# Amplifier_Output.net
KiCad netlist of a schematic drawn in Altium Designer
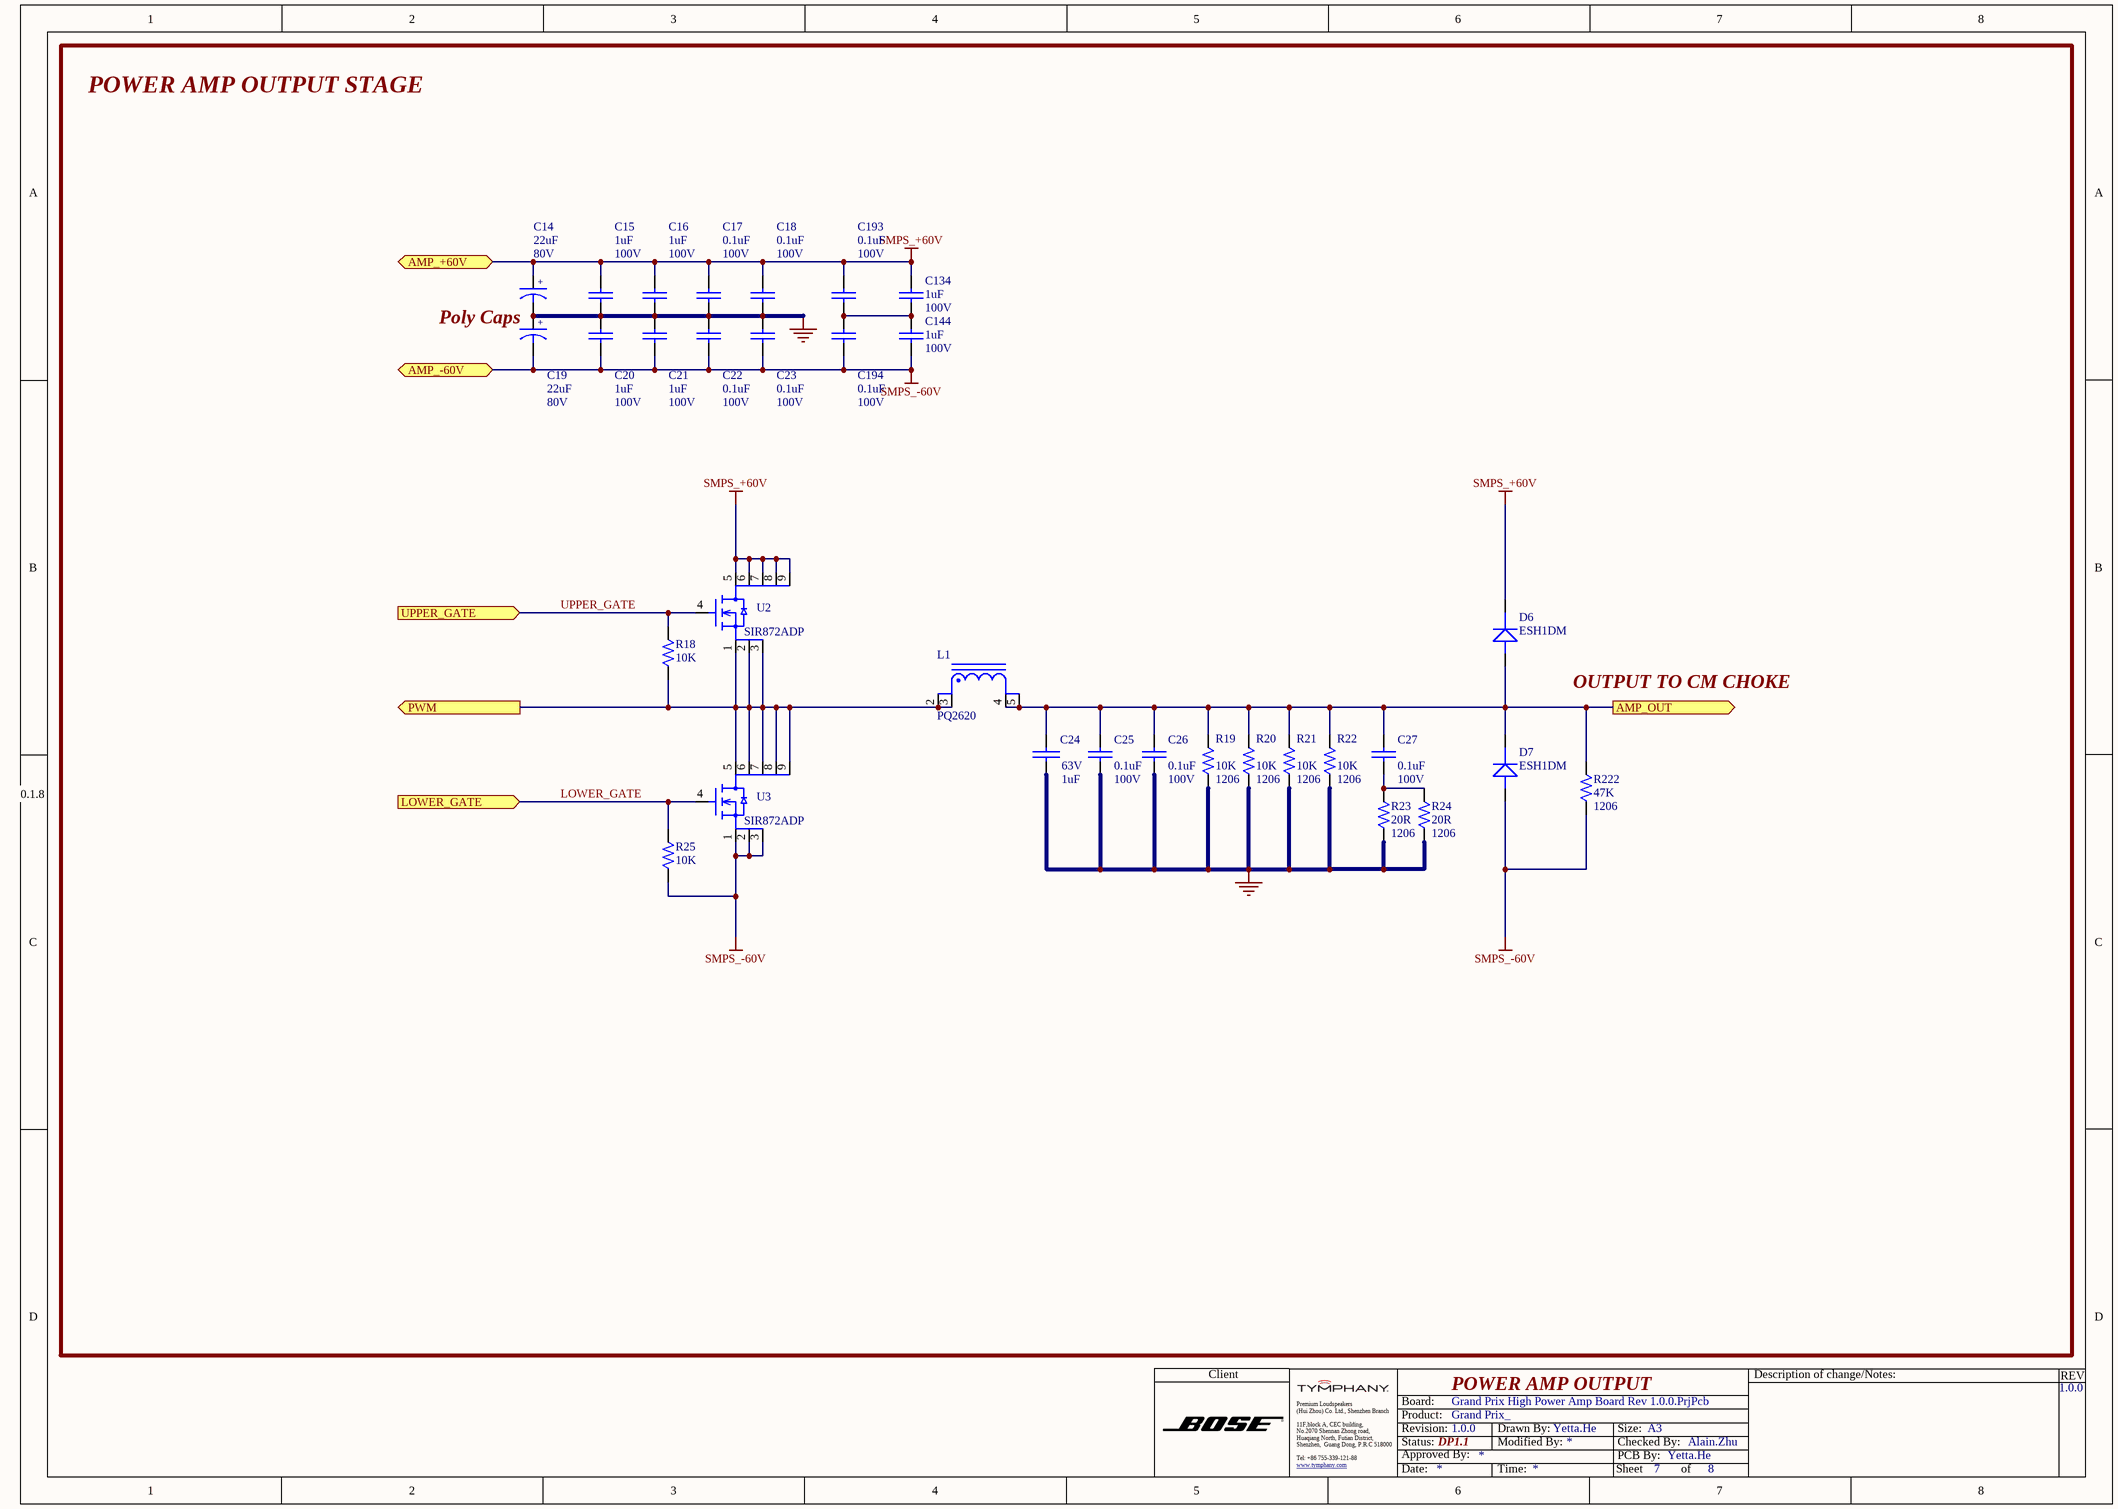
[diagram p0: Amplifier & Output.SchDoc]

(export (version "E")
  (design (tool "Eeschema 10.0.6"))
  (components
    (comp (ref "C14")
      (value "22uF")
      (footprint "CASE - F")
      (description "E 22UF 80V +-20% 8*10 HBV220M1KTR-0810")
      (fields
        (field (name "MFG PART") "HBV220M1KTR-0810")
        (field (name "TOLERANCE") "20%")
        (field (name "VOLTAGE") "80V")
        (field (name "CREATE NAME") "Cherry")
      )
      (libsource (lib "Temporary") (part "CAP E 22uF 80V 20% SMD_HBV220M1KTR-0810"))
    )
    (comp (ref "C15")
      (value "1uF")
      (footprint "CAPC0805X125N-RW")
      (description "CAP 1.0UF 100V +-10% 0805X7S TDK L")
      (fields
        (field (name "MFG") "TDK")
        (field (name "TOLERANCE") "10%")
        (field (name "VOLTAGE") "100V")
        (field (name "CREATE_NAME") "Nathan")
      )
      (libsource (lib "P-Capacitors") (part "CAPC0805 1uF 100V 10%_X7S_TDK"))
    )
    (comp (ref "C16")
      (value "1uF")
      (footprint "CAPC0805X125N-RW")
      (description "CAP 1.0UF 100V +-10% 0805X7S TDK L")
      (fields
        (field (name "MFG") "TDK")
        (field (name "TOLERANCE") "10%")
        (field (name "VOLTAGE") "100V")
        (field (name "CREATE_NAME") "Nathan")
      )
      (libsource (lib "P-Capacitors") (part "CAPC0805 1uF 100V 10%_X7S_TDK"))
    )
    (comp (ref "C17")
      (value "0.1uF")
      (footprint "CAPC0603-RW")
      (description "CAP X7R .10UF 100V +-10% 0603 MURATA L")
      (fields
        (field (name "MFG") "MURATA")
        (field (name "TOLERANCE") "10%")
        (field (name "VOLTAGE") "100V")
        (field (name "CREATE_NAME") "Nathan")
      )
      (libsource (lib "P-Capacitors") (part "CAP0603 0.1uF 100V 10%_X7R_MURATA"))
    )
    (comp (ref "C18")
      (value "0.1uF")
      (footprint "CAPC0603-RW")
      (description "CAP X7R .10UF 100V +-10% 0603 MURATA L")
      (fields
        (field (name "MFG") "MURATA")
        (field (name "TOLERANCE") "10%")
        (field (name "VOLTAGE") "100V")
        (field (name "CREATE_NAME") "Nathan")
      )
      (libsource (lib "P-Capacitors") (part "CAP0603 0.1uF 100V 10%_X7R_MURATA"))
    )
    (comp (ref "C19")
      (value "22uF")
      (footprint "CASE - F")
      (description "E 22UF 80V +-20% 8*10 HBV220M1KTR-0810")
      (fields
        (field (name "MFG PART") "HBV220M1KTR-0810")
        (field (name "TOLERANCE") "20%")
        (field (name "VOLTAGE") "80V")
        (field (name "CREATE NAME") "Cherry")
      )
      (libsource (lib "Temporary") (part "CAP E 22uF 80V 20% SMD_HBV220M1KTR-0810"))
    )
    (comp (ref "C20")
      (value "1uF")
      (footprint "CAPC0805X125N-RW")
      (description "CAP 1.0UF 100V +-10% 0805X7S TDK L")
      (fields
        (field (name "MFG") "TDK")
        (field (name "TOLERANCE") "10%")
        (field (name "VOLTAGE") "100V")
        (field (name "CREATE_NAME") "Nathan")
      )
      (libsource (lib "P-Capacitors") (part "CAPC0805 1uF 100V 10%_X7S_TDK"))
    )
    (comp (ref "C21")
      (value "1uF")
      (footprint "CAPC0805X125N-RW")
      (description "CAP 1.0UF 100V +-10% 0805X7S TDK L")
      (fields
        (field (name "MFG") "TDK")
        (field (name "TOLERANCE") "10%")
        (field (name "VOLTAGE") "100V")
        (field (name "CREATE_NAME") "Nathan")
      )
      (libsource (lib "P-Capacitors") (part "CAPC0805 1uF 100V 10%_X7S_TDK"))
    )
    (comp (ref "C22")
      (value "0.1uF")
      (footprint "CAPC0603-RW")
      (description "CAP X7R .10UF 100V +-10% 0603 MURATA L")
      (fields
        (field (name "MFG") "MURATA")
        (field (name "TOLERANCE") "10%")
        (field (name "VOLTAGE") "100V")
        (field (name "CREATE_NAME") "Nathan")
      )
      (libsource (lib "P-Capacitors") (part "CAP0603 0.1uF 100V 10%_X7R_MURATA"))
    )
    (comp (ref "C23")
      (value "0.1uF")
      (footprint "CAPC0603-RW")
      (description "CAP X7R .10UF 100V +-10% 0603 MURATA L")
      (fields
        (field (name "MFG") "MURATA")
        (field (name "TOLERANCE") "10%")
        (field (name "VOLTAGE") "100V")
        (field (name "CREATE_NAME") "Nathan")
      )
      (libsource (lib "P-Capacitors") (part "CAP0603 0.1uF 100V 10%_X7R_MURATA"))
    )
    (comp (ref "C24")
      (value "1uF")
      (footprint "1uF 63V TDK MKP")
      (description "PLS-DIP 1UF 63V +-5% T B32529C0 K")
      (fields
        (field (name "MFG") "TDK")
        (field (name "MFG PART") "B32529C0")
        (field (name "VOLTAGE") "63V")
        (field (name "CREATE_NAME") "Yetta")
      )
      (libsource (lib "Yetta_Lib") (part "CAP E MKP 1uF 63V 5%"))
    )
    (comp (ref "C25")
      (value "0.1uF")
      (footprint "CAPC0603-RW")
      (description "CAP X7R .10UF 100V +-10% 0603 MURATA L")
      (fields
        (field (name "MFG") "MURATA")
        (field (name "TOLERANCE") "10%")
        (field (name "VOLTAGE") "100V")
        (field (name "CREATE_NAME") "Nathan")
      )
      (libsource (lib "P-Capacitors") (part "CAP0603 0.1uF 100V 10%_X7R_MURATA"))
    )
    (comp (ref "C26")
      (value "0.1uF")
      (footprint "CAPC0603-RW")
      (description "CAP X7R .10UF 100V +-10% 0603 MURATA L")
      (fields
        (field (name "MFG") "MURATA")
        (field (name "TOLERANCE") "10%")
        (field (name "VOLTAGE") "100V")
        (field (name "CREATE_NAME") "Nathan")
      )
      (libsource (lib "P-Capacitors") (part "CAP0603 0.1uF 100V 10%_X7R_MURATA"))
    )
    (comp (ref "C27")
      (value "0.1uF")
      (footprint "CAPC0603-RW")
      (description "CAP X7R .10UF 100V +-10% 0603 MURATA L")
      (fields
        (field (name "MFG") "MURATA")
        (field (name "TOLERANCE") "10%")
        (field (name "VOLTAGE") "100V")
        (field (name "CREATE_NAME") "Nathan")
      )
      (libsource (lib "P-Capacitors") (part "CAP0603 0.1uF 100V 10%_X7R_MURATA"))
    )
    (comp (ref "C134")
      (value "1uF")
      (footprint "CAPC0805X125N-RW")
      (description "CAP 1.0UF 100V +-10% 0805X7S TDK L")
      (fields
        (field (name "MFG") "TDK")
        (field (name "TOLERANCE") "10%")
        (field (name "VOLTAGE") "100V")
        (field (name "CREATE_NAME") "Nathan")
      )
      (libsource (lib "P-Capacitors") (part "CAPC0805 1uF 100V 10%_X7S_TDK"))
    )
    (comp (ref "C144")
      (value "1uF")
      (footprint "CAPC0805X125N-RW")
      (description "CAP 1.0UF 100V +-10% 0805X7S TDK L")
      (fields
        (field (name "MFG") "TDK")
        (field (name "TOLERANCE") "10%")
        (field (name "VOLTAGE") "100V")
        (field (name "CREATE_NAME") "Nathan")
      )
      (libsource (lib "P-Capacitors") (part "CAPC0805 1uF 100V 10%_X7S_TDK"))
    )
    (comp (ref "C193")
      (value "0.1uF")
      (footprint "CAPC0603-RW")
      (description "CAP X7R .10UF 100V +-10% 0603 MURATA L")
      (fields
        (field (name "MFG") "MURATA")
        (field (name "TOLERANCE") "10%")
        (field (name "VOLTAGE") "100V")
        (field (name "CREATE_NAME") "Nathan")
      )
      (libsource (lib "P-Capacitors") (part "CAP0603 0.1uF 100V 10%_X7R_MURATA"))
    )
    (comp (ref "C194")
      (value "0.1uF")
      (footprint "CAPC0603-RW")
      (description "CAP X7R .10UF 100V +-10% 0603 MURATA L")
      (fields
        (field (name "MFG") "MURATA")
        (field (name "TOLERANCE") "10%")
        (field (name "VOLTAGE") "100V")
        (field (name "CREATE_NAME") "Nathan")
      )
      (libsource (lib "P-Capacitors") (part "CAP0603 0.1uF 100V 10%_X7R_MURATA"))
    )
    (comp (ref "D6")
      (value "T571002680204")
      (footprint "Micro SMA")
      (description "DIODE 200V 1.0A ESH1DM TSC G")
      (fields
        (field (name "MFG") "TSC")
        (field (name "VOLTAGE") "200V")
        (field (name "MFG PART") "ESH1DM")
        (field (name "CREATE_NAME") "Tom")
      )
      (libsource (lib "R-Semiconductors") (part "ESH1DM"))
    )
    (comp (ref "D7")
      (value "T571002680204")
      (footprint "Micro SMA")
      (description "DIODE 200V 1.0A ESH1DM TSC G")
      (fields
        (field (name "MFG") "TSC")
        (field (name "VOLTAGE") "200V")
        (field (name "MFG PART") "ESH1DM")
        (field (name "CREATE_NAME") "Tom")
      )
      (libsource (lib "R-Semiconductors") (part "ESH1DM"))
    )
    (comp (ref "L1")
      (value "PQ2620")
      (footprint "PQ2620")
      (description "INDUCTOR 11uH")
      (fields
        (field (name "MFG") "Gloria")
        (field (name "TOLERANCE") "10%")
        (field (name "MFG PART") "PQ2620")
      )
      (libsource (lib "Yetta_Lib") (part "PQ2620"))
    )
    (comp (ref "R18")
      (value "10K")
      (footprint "0603-RW")
      (description "GP CHIP RES. 10K OHM 1/10W 1% 0603")
      (fields (field (name "POWER") "1/10W") (field (name "Comment") "QCF011030-1002"))
      (libsource (lib "Q-Resistors") (part "RES0603 1/10W 1% 10K OHM"))
    )
    (comp (ref "R19")
      (value "10K")
      (footprint "1206-RW")
      (description "GP CHIP RES. 10K OHM 1/4  W 1% TF 1206")
      (fields
        (field (name "POWER") "1/4W")
        (field (name "PACKAGE") "1206")
        (field (name "Comment") "QCF041010-1002")
      )
      (libsource (lib "Q-Resistors") (part "RES1206 1/4W 1% 10K OHM"))
    )
    (comp (ref "R20")
      (value "10K")
      (footprint "1206-RW")
      (description "GP CHIP RES. 10K OHM 1/4  W 1% TF 1206")
      (fields
        (field (name "POWER") "1/4W")
        (field (name "PACKAGE") "1206")
        (field (name "Comment") "QCF041010-1002")
      )
      (libsource (lib "Q-Resistors") (part "RES1206 1/4W 1% 10K OHM"))
    )
    (comp (ref "R21")
      (value "10K")
      (footprint "1206-RW")
      (description "GP CHIP RES. 10K OHM 1/4  W 1% TF 1206")
      (fields
        (field (name "POWER") "1/4W")
        (field (name "PACKAGE") "1206")
        (field (name "Comment") "QCF041010-1002")
      )
      (libsource (lib "Q-Resistors") (part "RES1206 1/4W 1% 10K OHM"))
    )
    (comp (ref "R22")
      (value "10K")
      (footprint "1206-RW")
      (description "GP CHIP RES. 10K OHM 1/4  W 1% TF 1206")
      (fields
        (field (name "POWER") "1/4W")
        (field (name "PACKAGE") "1206")
        (field (name "Comment") "QCF041010-1002")
      )
      (libsource (lib "Q-Resistors") (part "RES1206 1/4W 1% 10K OHM"))
    )
    (comp (ref "R23")
      (value "20R")
      (footprint "1206-RW")
      (description "CHIP 20 OHM 100PPM +-1% 1206 WALS L")
      (fields
        (field (name "POWER") "1/4W")
        (field (name "MFG") "WALSIN (華新)")
        (field (name "PACKAGE") "1206")
      )
      (libsource (lib "Q-Resistors") (part "RES1206 1/4W 1% 20 OHM"))
    )
    (comp (ref "R24")
      (value "20R")
      (footprint "1206-RW")
      (description "CHIP 20 OHM 100PPM +-1% 1206 WALS L")
      (fields
        (field (name "POWER") "1/4W")
        (field (name "MFG") "WALSIN (華新)")
        (field (name "PACKAGE") "1206")
      )
      (libsource (lib "Q-Resistors") (part "RES1206 1/4W 1% 20 OHM"))
    )
    (comp (ref "R25")
      (value "10K")
      (footprint "0603-RW")
      (description "GP CHIP RES. 10K OHM 1/10W 1% 0603")
      (fields (field (name "POWER") "1/10W") (field (name "Comment") "QCF011030-1002"))
      (libsource (lib "Q-Resistors") (part "RES0603 1/10W 1% 10K OHM"))
    )
    (comp (ref "R222")
      (value "47K")
      (footprint "1206-RW")
      (description "CHIP RES. 47K OHM 1206 1%")
      (fields
        (field (name "POWER") "1/4W")
        (field (name "PACKAGE") "1206")
        (field (name "Comment") "QCF041010-4702")
      )
      (libsource (lib "Q-Resistors") (part "RES1206 1/4W 1% 47K OHM"))
    )
    (comp (ref "U2")
      (value "RCM000872-1001")
      (footprint "DFN8(5X6)")
      (description "N-Channel  MOSFET SO-8 SiR872ADP 150V(D-S)")
      (fields
        (field (name "MFG") "VISHAY")
        (field (name "VOLTAGE") "150V")
        (field (name "MFG PART") "SIR872ADP")
        (field (name "CREATE_NAME") "Nathan")
      )
      (libsource (lib "R-Semiconductors") (part "SIR872ADP"))
    )
    (comp (ref "U3")
      (value "RCM000872-1001")
      (footprint "DFN8(5X6)")
      (description "N-Channel  MOSFET SO-8 SiR872ADP 150V(D-S)")
      (fields
        (field (name "MFG") "VISHAY")
        (field (name "VOLTAGE") "150V")
        (field (name "MFG PART") "SIR872ADP")
        (field (name "CREATE_NAME") "Nathan")
      )
      (libsource (lib "R-Semiconductors") (part "SIR872ADP"))
    )
  )
  (nets
    (net (code "1") (name "/AMP_OUT") (class "Default")
      (node (ref "C24") (pin "1") (pinfunction "1_1") (pintype "passive"))
      (node (ref "C25") (pin "1") (pinfunction "1_1") (pintype "passive"))
      (node (ref "C26") (pin "1") (pinfunction "1_1") (pintype "passive"))
      (node (ref "C27") (pin "1") (pinfunction "1_1") (pintype "passive"))
      (node (ref "D6") (pin "1") (pinfunction "A_1") (pintype "passive"))
      (node (ref "D7") (pin "2") (pinfunction "K_2") (pintype "passive"))
      (node (ref "L1") (pin "4") (pinfunction "4_4") (pintype "passive"))
      (node (ref "L1") (pin "5") (pinfunction "5_5") (pintype "passive"))
      (node (ref "R19") (pin "2") (pinfunction "2_2") (pintype "passive"))
      (node (ref "R20") (pin "2") (pinfunction "2_2") (pintype "passive"))
      (node (ref "R21") (pin "2") (pinfunction "2_2") (pintype "passive"))
      (node (ref "R22") (pin "2") (pinfunction "2_2") (pintype "passive"))
      (node (ref "R222") (pin "2") (pinfunction "2_2") (pintype "passive"))
    )
    (net (code "2") (name "/LOWER_GATE") (class "Default")
      (node (ref "R25") (pin "2") (pinfunction "2_2") (pintype "passive"))
      (node (ref "U3") (pin "4") (pinfunction "G_4") (pintype "passive"))
    )
    (net (code "3") (name "/PWM") (class "Default")
      (node (ref "L1") (pin "2") (pinfunction "2_2") (pintype "passive"))
      (node (ref "L1") (pin "3") (pinfunction "3_3") (pintype "passive"))
      (node (ref "R18") (pin "1") (pinfunction "1_1") (pintype "passive"))
      (node (ref "U2") (pin "1") (pinfunction "S_1") (pintype "passive"))
      (node (ref "U2") (pin "2") (pinfunction "S_2") (pintype "passive"))
      (node (ref "U2") (pin "3") (pinfunction "S_3") (pintype "passive"))
      (node (ref "U3") (pin "5") (pinfunction "D_5") (pintype "passive"))
      (node (ref "U3") (pin "6") (pinfunction "D_6") (pintype "passive"))
      (node (ref "U3") (pin "7") (pinfunction "D_7") (pintype "passive"))
      (node (ref "U3") (pin "8") (pinfunction "D_8") (pintype "passive"))
      (node (ref "U3") (pin "9") (pinfunction "D_9") (pintype "passive"))
    )
    (net (code "4") (name "/UPPER_GATE") (class "Default")
      (node (ref "R18") (pin "2") (pinfunction "2_2") (pintype "passive"))
      (node (ref "U2") (pin "4") (pinfunction "G_4") (pintype "passive"))
    )
    (net (code "5") (name "GND") (class "Default")
      (node (ref "C14") (pin "2") (pinfunction "2_2") (pintype "passive"))
      (node (ref "C15") (pin "2") (pinfunction "2_2") (pintype "passive"))
      (node (ref "C16") (pin "2") (pinfunction "2_2") (pintype "passive"))
      (node (ref "C17") (pin "2") (pinfunction "2_2") (pintype "passive"))
      (node (ref "C18") (pin "2") (pinfunction "2_2") (pintype "passive"))
      (node (ref "C19") (pin "1") (pinfunction "1_1") (pintype "passive"))
      (node (ref "C20") (pin "1") (pinfunction "1_1") (pintype "passive"))
      (node (ref "C21") (pin "1") (pinfunction "1_1") (pintype "passive"))
      (node (ref "C22") (pin "1") (pinfunction "1_1") (pintype "passive"))
      (node (ref "C23") (pin "1") (pinfunction "1_1") (pintype "passive"))
      (node (ref "C24") (pin "2") (pinfunction "2_2") (pintype "passive"))
      (node (ref "C25") (pin "2") (pinfunction "2_2") (pintype "passive"))
      (node (ref "C26") (pin "2") (pinfunction "2_2") (pintype "passive"))
      (node (ref "R19") (pin "1") (pinfunction "1_1") (pintype "passive"))
      (node (ref "R20") (pin "1") (pinfunction "1_1") (pintype "passive"))
      (node (ref "R21") (pin "1") (pinfunction "1_1") (pintype "passive"))
      (node (ref "R22") (pin "1") (pinfunction "1_1") (pintype "passive"))
      (node (ref "R23") (pin "1") (pinfunction "1_1") (pintype "passive"))
      (node (ref "R24") (pin "1") (pinfunction "1_1") (pintype "passive"))
    )
    (net (code "6") (name "Net-(C27-Pad2)") (class "Default")
      (node (ref "C27") (pin "2") (pinfunction "2_2") (pintype "passive"))
      (node (ref "R23") (pin "2") (pinfunction "2_2") (pintype "passive"))
      (node (ref "R24") (pin "2") (pinfunction "2_2") (pintype "passive"))
    )
    (net (code "7") (name "Net-(C134-Pad2)") (class "Default")
      (node (ref "C134") (pin "2") (pinfunction "2_2") (pintype "passive"))
      (node (ref "C144") (pin "1") (pinfunction "1_1") (pintype "passive"))
      (node (ref "C193") (pin "2") (pinfunction "2_2") (pintype "passive"))
      (node (ref "C194") (pin "1") (pinfunction "1_1") (pintype "passive"))
    )
    (net (code "8") (name "SMPS_+60V") (class "Default")
      (node (ref "C134") (pin "1") (pinfunction "1_1") (pintype "passive"))
      (node (ref "C14") (pin "1") (pinfunction "1_1") (pintype "passive"))
      (node (ref "C15") (pin "1") (pinfunction "1_1") (pintype "passive"))
      (node (ref "C16") (pin "1") (pinfunction "1_1") (pintype "passive"))
      (node (ref "C17") (pin "1") (pinfunction "1_1") (pintype "passive"))
      (node (ref "C18") (pin "1") (pinfunction "1_1") (pintype "passive"))
      (node (ref "C193") (pin "1") (pinfunction "1_1") (pintype "passive"))
      (node (ref "D6") (pin "2") (pinfunction "K_2") (pintype "passive"))
      (node (ref "U2") (pin "5") (pinfunction "D_5") (pintype "passive"))
      (node (ref "U2") (pin "6") (pinfunction "D_6") (pintype "passive"))
      (node (ref "U2") (pin "7") (pinfunction "D_7") (pintype "passive"))
      (node (ref "U2") (pin "8") (pinfunction "D_8") (pintype "passive"))
      (node (ref "U2") (pin "9") (pinfunction "D_9") (pintype "passive"))
    )
    (net (code "9") (name "SMPS_-60V") (class "Default")
      (node (ref "C144") (pin "2") (pinfunction "2_2") (pintype "passive"))
      (node (ref "C19") (pin "2") (pinfunction "2_2") (pintype "passive"))
      (node (ref "C194") (pin "2") (pinfunction "2_2") (pintype "passive"))
      (node (ref "C20") (pin "2") (pinfunction "2_2") (pintype "passive"))
      (node (ref "C21") (pin "2") (pinfunction "2_2") (pintype "passive"))
      (node (ref "C22") (pin "2") (pinfunction "2_2") (pintype "passive"))
      (node (ref "C23") (pin "2") (pinfunction "2_2") (pintype "passive"))
      (node (ref "D7") (pin "1") (pinfunction "A_1") (pintype "passive"))
      (node (ref "R222") (pin "1") (pinfunction "1_1") (pintype "passive"))
      (node (ref "R25") (pin "1") (pinfunction "1_1") (pintype "passive"))
      (node (ref "U3") (pin "1") (pinfunction "S_1") (pintype "passive"))
      (node (ref "U3") (pin "2") (pinfunction "S_2") (pintype "passive"))
      (node (ref "U3") (pin "3") (pinfunction "S_3") (pintype "passive"))
    )
  )
)
